# P1.net
KiCad netlist of a schematic drawn in Altium Designer
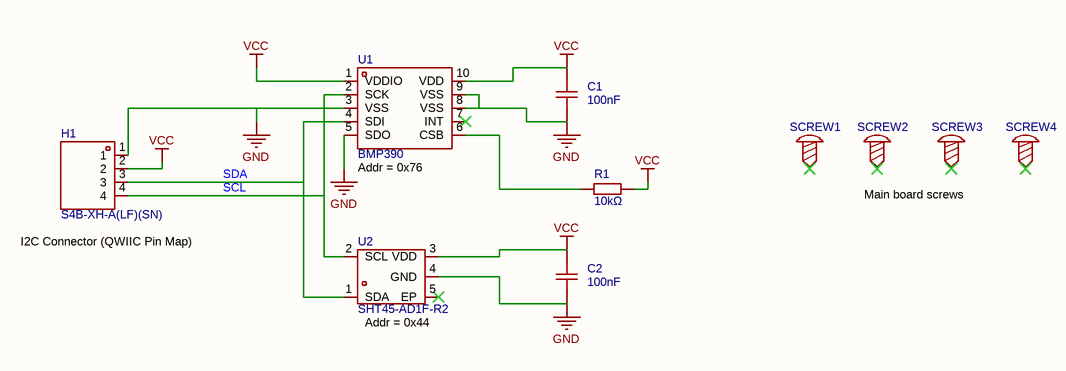
[diagram p0: P1.schdoc]

(export (version "E")
  (design (tool "Eeschema 10.0.6"))
  (components
    (comp (ref "C1")
      (value "100nF")
      (footprint "C0402")
      (description "Capacitance:100nF Tolerance:±10% Tolerance:±10% Voltage Rating:16V Temperature Coefficient:X7R")
      (fields (field (name "MANUFACTURER") "SAMSUNG(三星)") (field (name "MANUFACTURERPART") "CL05B104KO5NNNC"))
      (libsource (lib "altium-import") (part "root_1_CL05B104KO5NNNC_"))
    )
    (comp (ref "C2")
      (value "100nF")
      (footprint "C0402")
      (description "Capacitance:100nF Tolerance:±10% Tolerance:±10% Voltage Rating:16V Temperature Coefficient:X7R")
      (fields (field (name "MANUFACTURER") "SAMSUNG(三星)") (field (name "MANUFACTURERPART") "CL05B104KO5NNNC"))
      (libsource (lib "altium-import") (part "root_1_CL05B104KO5NNNC_"))
    )
    (comp (ref "H1")
      (value "S4B-XH-A(LF)(SN)")
      (footprint "CONN-TH_S4B-XH-A-LF-SN")
      (fields (field (name "MANUFACTURER") "JST"))
      (libsource (lib "altium-import") (part "root_0_mirrored_S4B-XH-A(LF)(SN)_"))
    )
    (comp (ref "R1")
      (value "10kΩ")
      (footprint "R0402")
      (fields
        (field (name "MANUFACTURER") "VO(翔胜)")
        (field (name "MANUFACTURERPART") "SCR0402F10K")
        (field (name "TOLERANCE") "±1%")
      )
      (libsource (lib "altium-import") (part "root_0_SCR0402F10K_"))
    )
    (comp (ref "SCREW1")
      (value "~")
      (footprint "Screw-Hole-M3")
      (libsource (lib "altium-import") (part "root_0_Screw-Hole-M3_"))
    )
    (comp (ref "SCREW2")
      (value "~")
      (footprint "Screw-Hole-M3")
      (libsource (lib "altium-import") (part "root_0_Screw-Hole-M3_"))
    )
    (comp (ref "SCREW3")
      (value "~")
      (footprint "Screw-Hole-M3")
      (libsource (lib "altium-import") (part "root_0_Screw-Hole-M3_"))
    )
    (comp (ref "SCREW4")
      (value "~")
      (footprint "Screw-Hole-M3")
      (libsource (lib "altium-import") (part "root_0_Screw-Hole-M3_"))
    )
    (comp (ref "U1")
      (value "BMP390")
      (footprint "LGA-10_L2.0-W2.0-P0.50-BL")
      (libsource (lib "altium-import") (part "root_0_BMP390_"))
    )
    (comp (ref "U2")
      (value "SHT45-AD1F-R2")
      (footprint "DFN-4_L1.5-W1.5-P0.8-TL-EP")
      (fields (field (name "MANUFACTURER") "Sensirion(瑞士盛思锐)"))
      (libsource (lib "altium-import") (part "root_2_mirrored_SHT45-AD1F-R2_"))
    )
  )
  (nets
    (net (code "1") (name "/SCL") (class "Default")
      (node (ref "H1") (pin "4") (pinfunction "4_4") (pintype "passive"))
      (node (ref "U1") (pin "2") (pinfunction "SCK_2") (pintype "passive"))
      (node (ref "U2") (pin "2") (pinfunction "SCL_2") (pintype "passive"))
    )
    (net (code "2") (name "/SDA") (class "Default")
      (node (ref "H1") (pin "3") (pinfunction "3_3") (pintype "passive"))
      (node (ref "U1") (pin "4") (pinfunction "SDI_4") (pintype "passive"))
      (node (ref "U2") (pin "1") (pinfunction "SDA_1") (pintype "passive"))
    )
    (net (code "3") (name "GND") (class "Default")
      (node (ref "C1") (pin "2") (pinfunction "2_2") (pintype "passive"))
      (node (ref "C2") (pin "2") (pinfunction "2_2") (pintype "passive"))
      (node (ref "H1") (pin "1") (pinfunction "1_1") (pintype "passive"))
      (node (ref "U1") (pin "3") (pinfunction "VSS_3") (pintype "passive"))
      (node (ref "U1") (pin "5") (pinfunction "SDO_5") (pintype "passive"))
      (node (ref "U1") (pin "8") (pinfunction "VSS_8") (pintype "passive"))
      (node (ref "U1") (pin "9") (pinfunction "VSS_9") (pintype "passive"))
      (node (ref "U2") (pin "4") (pinfunction "GND_4") (pintype "passive"))
    )
    (net (code "4") (name "Net-(U1-CSB)") (class "Default")
      (node (ref "R1") (pin "1") (pinfunction "1_1") (pintype "passive"))
      (node (ref "U1") (pin "6") (pinfunction "CSB_6") (pintype "passive"))
    )
    (net (code "5") (name "VCC") (class "Default")
      (node (ref "C1") (pin "1") (pinfunction "1_1") (pintype "passive"))
      (node (ref "C2") (pin "1") (pinfunction "1_1") (pintype "passive"))
      (node (ref "H1") (pin "2") (pinfunction "2_2") (pintype "passive"))
      (node (ref "R1") (pin "2") (pinfunction "2_2") (pintype "passive"))
      (node (ref "U1") (pin "1") (pinfunction "VDDIO_1") (pintype "passive"))
      (node (ref "U1") (pin "10") (pinfunction "VDD_10") (pintype "passive"))
      (node (ref "U2") (pin "3") (pinfunction "VDD_3") (pintype "passive"))
    )
    (net (code "6") (name "unconnected-(SCREW1-Pad1)") (class "Default")
      (node (ref "SCREW1") (pin "1") (pinfunction "1_1") (pintype "passive+no_connect"))
    )
    (net (code "7") (name "unconnected-(SCREW2-Pad1)") (class "Default")
      (node (ref "SCREW2") (pin "1") (pinfunction "1_1") (pintype "passive+no_connect"))
    )
    (net (code "8") (name "unconnected-(SCREW3-Pad1)") (class "Default")
      (node (ref "SCREW3") (pin "1") (pinfunction "1_1") (pintype "passive+no_connect"))
    )
    (net (code "9") (name "unconnected-(SCREW4-Pad1)") (class "Default")
      (node (ref "SCREW4") (pin "1") (pinfunction "1_1") (pintype "passive+no_connect"))
    )
    (net (code "10") (name "unconnected-(U1-INT-Pad7)") (class "Default")
      (node (ref "U1") (pin "7") (pinfunction "INT_7") (pintype "passive+no_connect"))
    )
    (net (code "11") (name "unconnected-(U2-EP-Pad5)") (class "Default")
      (node (ref "U2") (pin "5") (pinfunction "EP_5") (pintype "passive+no_connect"))
    )
  )
)
